# contactor.net
KiCad netlist of a schematic drawn in EAGLE
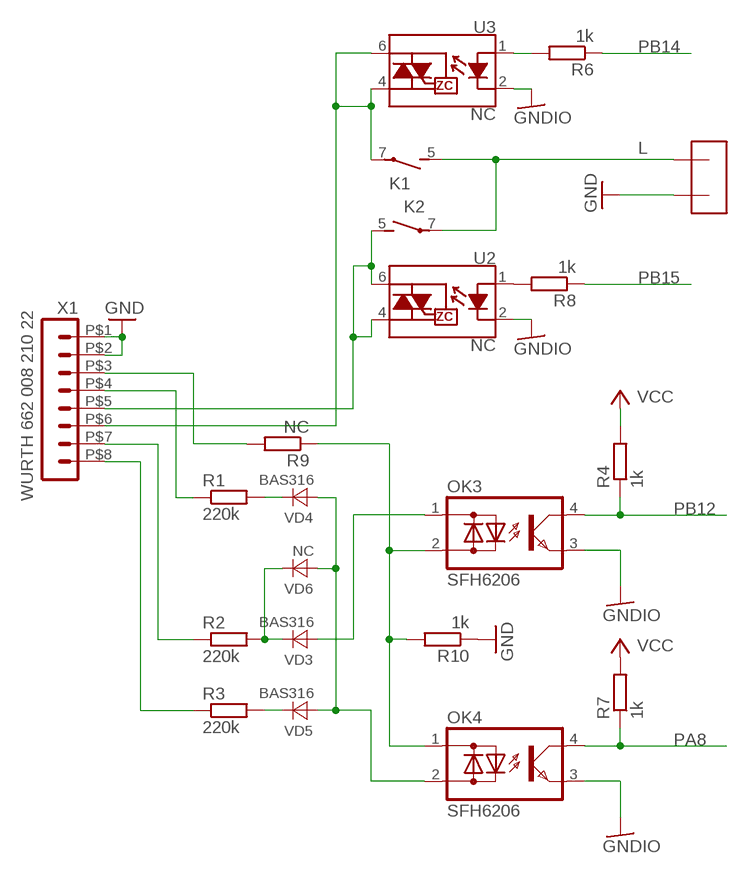
[diagram p0: schematic, sheet 1]

(export (version "E")
  (design (tool "Eeschema 10.0.6"))
  (components
    (comp (ref "K1")
      (value "G6D-1A-ASI5VDC")
      (footprint "eagle-import:G6D")
      (libsource (lib "eagle-import") (part "G6D?-1A-ASI5VDC"))
    )
    (comp (ref "K2")
      (value "NC")
      (footprint "eagle-import:G6D")
      (libsource (lib "eagle-import") (part "G6D?-1A-ASI5VDC"))
    )
    (comp (ref "OK3")
      (value "SFH6206")
      (footprint "eagle-import:DIL4-SMD")
      (fields (field (name "MF") "VISHAY/TELEFUNKEN") (field (name "MPN") "SFH6206-3"))
      (libsource (lib "eagle-import") (part "SFH6206"))
    )
    (comp (ref "OK4")
      (value "SFH6206")
      (footprint "eagle-import:DIL4-SMD")
      (fields (field (name "MF") "VISHAY/TELEFUNKEN") (field (name "MPN") "SFH6206-3"))
      (libsource (lib "eagle-import") (part "SFH6206"))
    )
    (comp (ref "R1")
      (value "220k")
      (footprint "eagle-import:R1210")
      (libsource (lib "eagle-import") (part "R-EU_R1210"))
    )
    (comp (ref "R2")
      (value "220k")
      (footprint "eagle-import:R1210")
      (libsource (lib "eagle-import") (part "R-EU_R1210"))
    )
    (comp (ref "R3")
      (value "220k")
      (footprint "eagle-import:R1210")
      (libsource (lib "eagle-import") (part "R-EU_R1210"))
    )
    (comp (ref "R4")
      (value "1k")
      (footprint "eagle-import:R0805")
      (libsource (lib "eagle-import") (part "R-EU_R0805"))
    )
    (comp (ref "R6")
      (value "1k")
      (footprint "eagle-import:R0805")
      (libsource (lib "eagle-import") (part "R-EU_R0805"))
    )
    (comp (ref "R7")
      (value "1k")
      (footprint "eagle-import:R0805")
      (libsource (lib "eagle-import") (part "R-EU_R0805"))
    )
    (comp (ref "R8")
      (value "1k")
      (footprint "eagle-import:R0805")
      (libsource (lib "eagle-import") (part "R-EU_R0805"))
    )
    (comp (ref "R9")
      (value "NC")
      (footprint "eagle-import:R0805")
      (libsource (lib "eagle-import") (part "R-EU_R0805"))
    )
    (comp (ref "R10")
      (value "1k")
      (footprint "eagle-import:R0805")
      (libsource (lib "eagle-import") (part "R-EU_R0805"))
    )
    (comp (ref "U$6")
      (value "2 PIN STRIP M")
      (footprint "eagle-import:STRIP_NOMIDDLE")
      (libsource (lib "eagle-import") (part "ISOLATED_2P"))
    )
    (comp (ref "U2")
      (value "NC")
      (footprint "eagle-import:DIP8SMD")
      (libsource (lib "eagle-import") (part "TRIAC_OPTOCOUPLER-MOC3063SM"))
    )
    (comp (ref "U3")
      (value "NC")
      (footprint "eagle-import:DIP8SMD")
      (libsource (lib "eagle-import") (part "TRIAC_OPTOCOUPLER-MOC3063SM"))
    )
    (comp (ref "VD3")
      (value "BAS316")
      (footprint "eagle-import:SOD323")
      (libsource (lib "eagle-import") (part "DIODE-STANDARD-SOD323"))
    )
    (comp (ref "VD4")
      (value "BAS316")
      (footprint "eagle-import:SOD323")
      (libsource (lib "eagle-import") (part "DIODE-STANDARD-SOD323"))
    )
    (comp (ref "VD5")
      (value "BAS316")
      (footprint "eagle-import:SOD323")
      (libsource (lib "eagle-import") (part "DIODE-STANDARD-SOD323"))
    )
    (comp (ref "VD6")
      (value "NC")
      (footprint "eagle-import:SOD323")
      (libsource (lib "eagle-import") (part "DIODE-STANDARD-SOD323"))
    )
    (comp (ref "X1")
      (value "WURTH 662 008 210 22")
      (footprint "eagle-import:43045-0800")
      (libsource (lib "eagle-import") (part "HEADER_POS8_?43045-0800"))
    )
  )
  (nets
    (net (code "1") (name "/L") (class "Default")
      (node (ref "K1") (pin "5") (pinfunction "S_5") (pintype "passive"))
      (node (ref "K2") (pin "7") (pinfunction "P_7") (pintype "passive"))
      (node (ref "U$6") (pin "P$1") (pinfunction "P$1_P$1") (pintype "bidirectional"))
    )
    (net (code "2") (name "/PA8") (class "Default")
      (node (ref "OK4") (pin "4") (pinfunction "C_4") (pintype "passive"))
      (node (ref "R7") (pin "1") (pinfunction "1_1") (pintype "passive"))
    )
    (net (code "3") (name "/PB12") (class "Default")
      (node (ref "OK3") (pin "4") (pinfunction "C_4") (pintype "passive"))
      (node (ref "R4") (pin "1") (pinfunction "1_1") (pintype "passive"))
    )
    (net (code "4") (name "/PB14") (class "Default")
      (node (ref "R6") (pin "1") (pinfunction "1_1") (pintype "passive"))
    )
    (net (code "5") (name "/PB15") (class "Default")
      (node (ref "R8") (pin "1") (pinfunction "1_1") (pintype "passive"))
    )
    (net (code "6") (name "GND") (class "Default")
      (node (ref "R10") (pin "1") (pinfunction "1_1") (pintype "passive"))
      (node (ref "U$6") (pin "P$2") (pinfunction "P$2_P$2") (pintype "bidirectional"))
      (node (ref "X1") (pin "P$1") (pinfunction "1_P$1") (pintype "passive"))
      (node (ref "X1") (pin "P$2") (pinfunction "2_P$2") (pintype "passive"))
    )
    (net (code "7") (name "GNDIO") (class "Default")
      (node (ref "OK3") (pin "3") (pinfunction "E_3") (pintype "passive"))
      (node (ref "OK4") (pin "3") (pinfunction "E_3") (pintype "passive"))
      (node (ref "U2") (pin "2") (pinfunction "K_2") (pintype "bidirectional"))
      (node (ref "U3") (pin "2") (pinfunction "K_2") (pintype "bidirectional"))
    )
    (net (code "8") (name "Net-(K1B-P)") (class "Default")
      (node (ref "K1") (pin "7") (pinfunction "P_7") (pintype "passive"))
      (node (ref "U3") (pin "4") (pinfunction "T2_4") (pintype "bidirectional"))
      (node (ref "U3") (pin "6") (pinfunction "T1_6") (pintype "bidirectional"))
      (node (ref "X1") (pin "P$6") (pinfunction "6_P$6") (pintype "passive"))
    )
    (net (code "9") (name "Net-(K2B-S)") (class "Default")
      (node (ref "K2") (pin "5") (pinfunction "S_5") (pintype "passive"))
      (node (ref "U2") (pin "4") (pinfunction "T2_4") (pintype "bidirectional"))
      (node (ref "U2") (pin "6") (pinfunction "T1_6") (pintype "bidirectional"))
      (node (ref "X1") (pin "P$5") (pinfunction "5_P$5") (pintype "passive"))
    )
    (net (code "10") (name "Net-(OK3-AC1)") (class "Default")
      (node (ref "OK3") (pin "1") (pinfunction "AC1_1") (pintype "passive"))
      (node (ref "VD3") (pin "A") (pinfunction "A_A") (pintype "passive"))
    )
    (net (code "11") (name "Net-(OK3-AC2)") (class "Default")
      (node (ref "OK3") (pin "2") (pinfunction "AC2_2") (pintype "passive"))
      (node (ref "OK4") (pin "1") (pinfunction "AC1_1") (pintype "passive"))
      (node (ref "R10") (pin "2") (pinfunction "2_2") (pintype "passive"))
      (node (ref "R9") (pin "1") (pinfunction "1_1") (pintype "passive"))
    )
    (net (code "12") (name "Net-(OK4-AC2)") (class "Default")
      (node (ref "OK4") (pin "2") (pinfunction "AC2_2") (pintype "passive"))
      (node (ref "VD4") (pin "A") (pinfunction "A_A") (pintype "passive"))
      (node (ref "VD5") (pin "A") (pinfunction "A_A") (pintype "passive"))
      (node (ref "VD6") (pin "A") (pinfunction "A_A") (pintype "passive"))
    )
    (net (code "13") (name "Net-(R1-Pad2)") (class "Default")
      (node (ref "R1") (pin "2") (pinfunction "2_2") (pintype "passive"))
      (node (ref "VD4") (pin "C") (pinfunction "C_C") (pintype "passive"))
    )
    (net (code "14") (name "Net-(R2-Pad2)") (class "Default")
      (node (ref "R2") (pin "2") (pinfunction "2_2") (pintype "passive"))
      (node (ref "VD3") (pin "C") (pinfunction "C_C") (pintype "passive"))
      (node (ref "VD6") (pin "C") (pinfunction "C_C") (pintype "passive"))
    )
    (net (code "15") (name "Net-(R3-Pad2)") (class "Default")
      (node (ref "R3") (pin "2") (pinfunction "2_2") (pintype "passive"))
      (node (ref "VD5") (pin "C") (pinfunction "C_C") (pintype "passive"))
    )
    (net (code "16") (name "Net-(U2-A)") (class "Default")
      (node (ref "R8") (pin "2") (pinfunction "2_2") (pintype "passive"))
      (node (ref "U2") (pin "1") (pinfunction "A_1") (pintype "bidirectional"))
    )
    (net (code "17") (name "Net-(U3-A)") (class "Default")
      (node (ref "R6") (pin "2") (pinfunction "2_2") (pintype "passive"))
      (node (ref "U3") (pin "1") (pinfunction "A_1") (pintype "bidirectional"))
    )
    (net (code "18") (name "Net-(X1-3)") (class "Default")
      (node (ref "R9") (pin "2") (pinfunction "2_2") (pintype "passive"))
      (node (ref "X1") (pin "P$3") (pinfunction "3_P$3") (pintype "passive"))
    )
    (net (code "19") (name "Net-(X1-4)") (class "Default")
      (node (ref "R1") (pin "1") (pinfunction "1_1") (pintype "passive"))
      (node (ref "X1") (pin "P$4") (pinfunction "4_P$4") (pintype "passive"))
    )
    (net (code "20") (name "Net-(X1-7)") (class "Default")
      (node (ref "R2") (pin "1") (pinfunction "1_1") (pintype "passive"))
      (node (ref "X1") (pin "P$7") (pinfunction "7_P$7") (pintype "passive"))
    )
    (net (code "21") (name "Net-(X1-8)") (class "Default")
      (node (ref "R3") (pin "1") (pinfunction "1_1") (pintype "passive"))
      (node (ref "X1") (pin "P$8") (pinfunction "8_P$8") (pintype "passive"))
    )
    (net (code "22") (name "VCC") (class "Default")
      (node (ref "R4") (pin "2") (pinfunction "2_2") (pintype "passive"))
      (node (ref "R7") (pin "2") (pinfunction "2_2") (pintype "passive"))
    )
  )
)
